# 8-LEDx4.net
KiCad netlist of a schematic drawn in Altium Designer
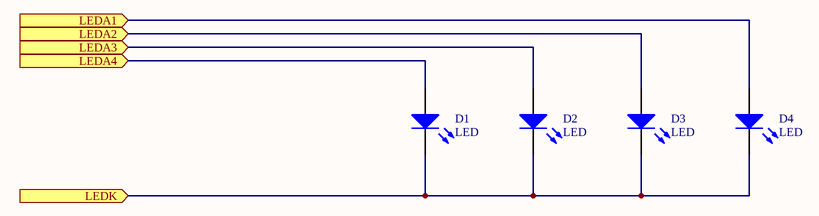
[diagram p0: 8-LEDx4.SchDoc]

(export (version "E")
  (design (tool "Eeschema 10.0.6"))
  (components
    (comp (ref "D1")
      (value "LED")
      (footprint "LED-0")
      (description "Diffused Green 3mm LED")
      (fields (field (name "PUBLISHER") "Altium Limited"))
      (libsource (lib "Miscellaneous Devices") (part "LED0"))
    )
    (comp (ref "D2")
      (value "LED")
      (footprint "LED-0")
      (description "Diffused Green 3mm LED")
      (fields (field (name "PUBLISHER") "Altium Limited"))
      (libsource (lib "Miscellaneous Devices") (part "LED0"))
    )
    (comp (ref "D3")
      (value "LED")
      (footprint "LED-0")
      (description "Diffused Green 3mm LED")
      (fields (field (name "PUBLISHER") "Altium Limited"))
      (libsource (lib "Miscellaneous Devices") (part "LED0"))
    )
    (comp (ref "D4")
      (value "LED")
      (footprint "LED-0")
      (description "Diffused Green 3mm LED")
      (fields (field (name "PUBLISHER") "Altium Limited"))
      (libsource (lib "Miscellaneous Devices") (part "LED0"))
    )
  )
  (nets
    (net (code "1") (name "/LEDA1") (class "Default")
      (node (ref "D4") (pin "1") (pinfunction "A_1") (pintype "passive"))
    )
    (net (code "2") (name "/LEDA2") (class "Default")
      (node (ref "D3") (pin "1") (pinfunction "A_1") (pintype "passive"))
    )
    (net (code "3") (name "/LEDA3") (class "Default")
      (node (ref "D2") (pin "1") (pinfunction "A_1") (pintype "passive"))
    )
    (net (code "4") (name "/LEDA4") (class "Default")
      (node (ref "D1") (pin "1") (pinfunction "A_1") (pintype "passive"))
    )
    (net (code "5") (name "/LEDK") (class "Default")
      (node (ref "D1") (pin "2") (pinfunction "K_2") (pintype "passive"))
      (node (ref "D2") (pin "2") (pinfunction "K_2") (pintype "passive"))
      (node (ref "D3") (pin "2") (pinfunction "K_2") (pintype "passive"))
      (node (ref "D4") (pin "2") (pinfunction "K_2") (pintype "passive"))
    )
  )
)
